# SCH_RTK2B_Micro_F9P_Breakout_Board_2023-.net
KiCad netlist of a schematic drawn in EasyEDA
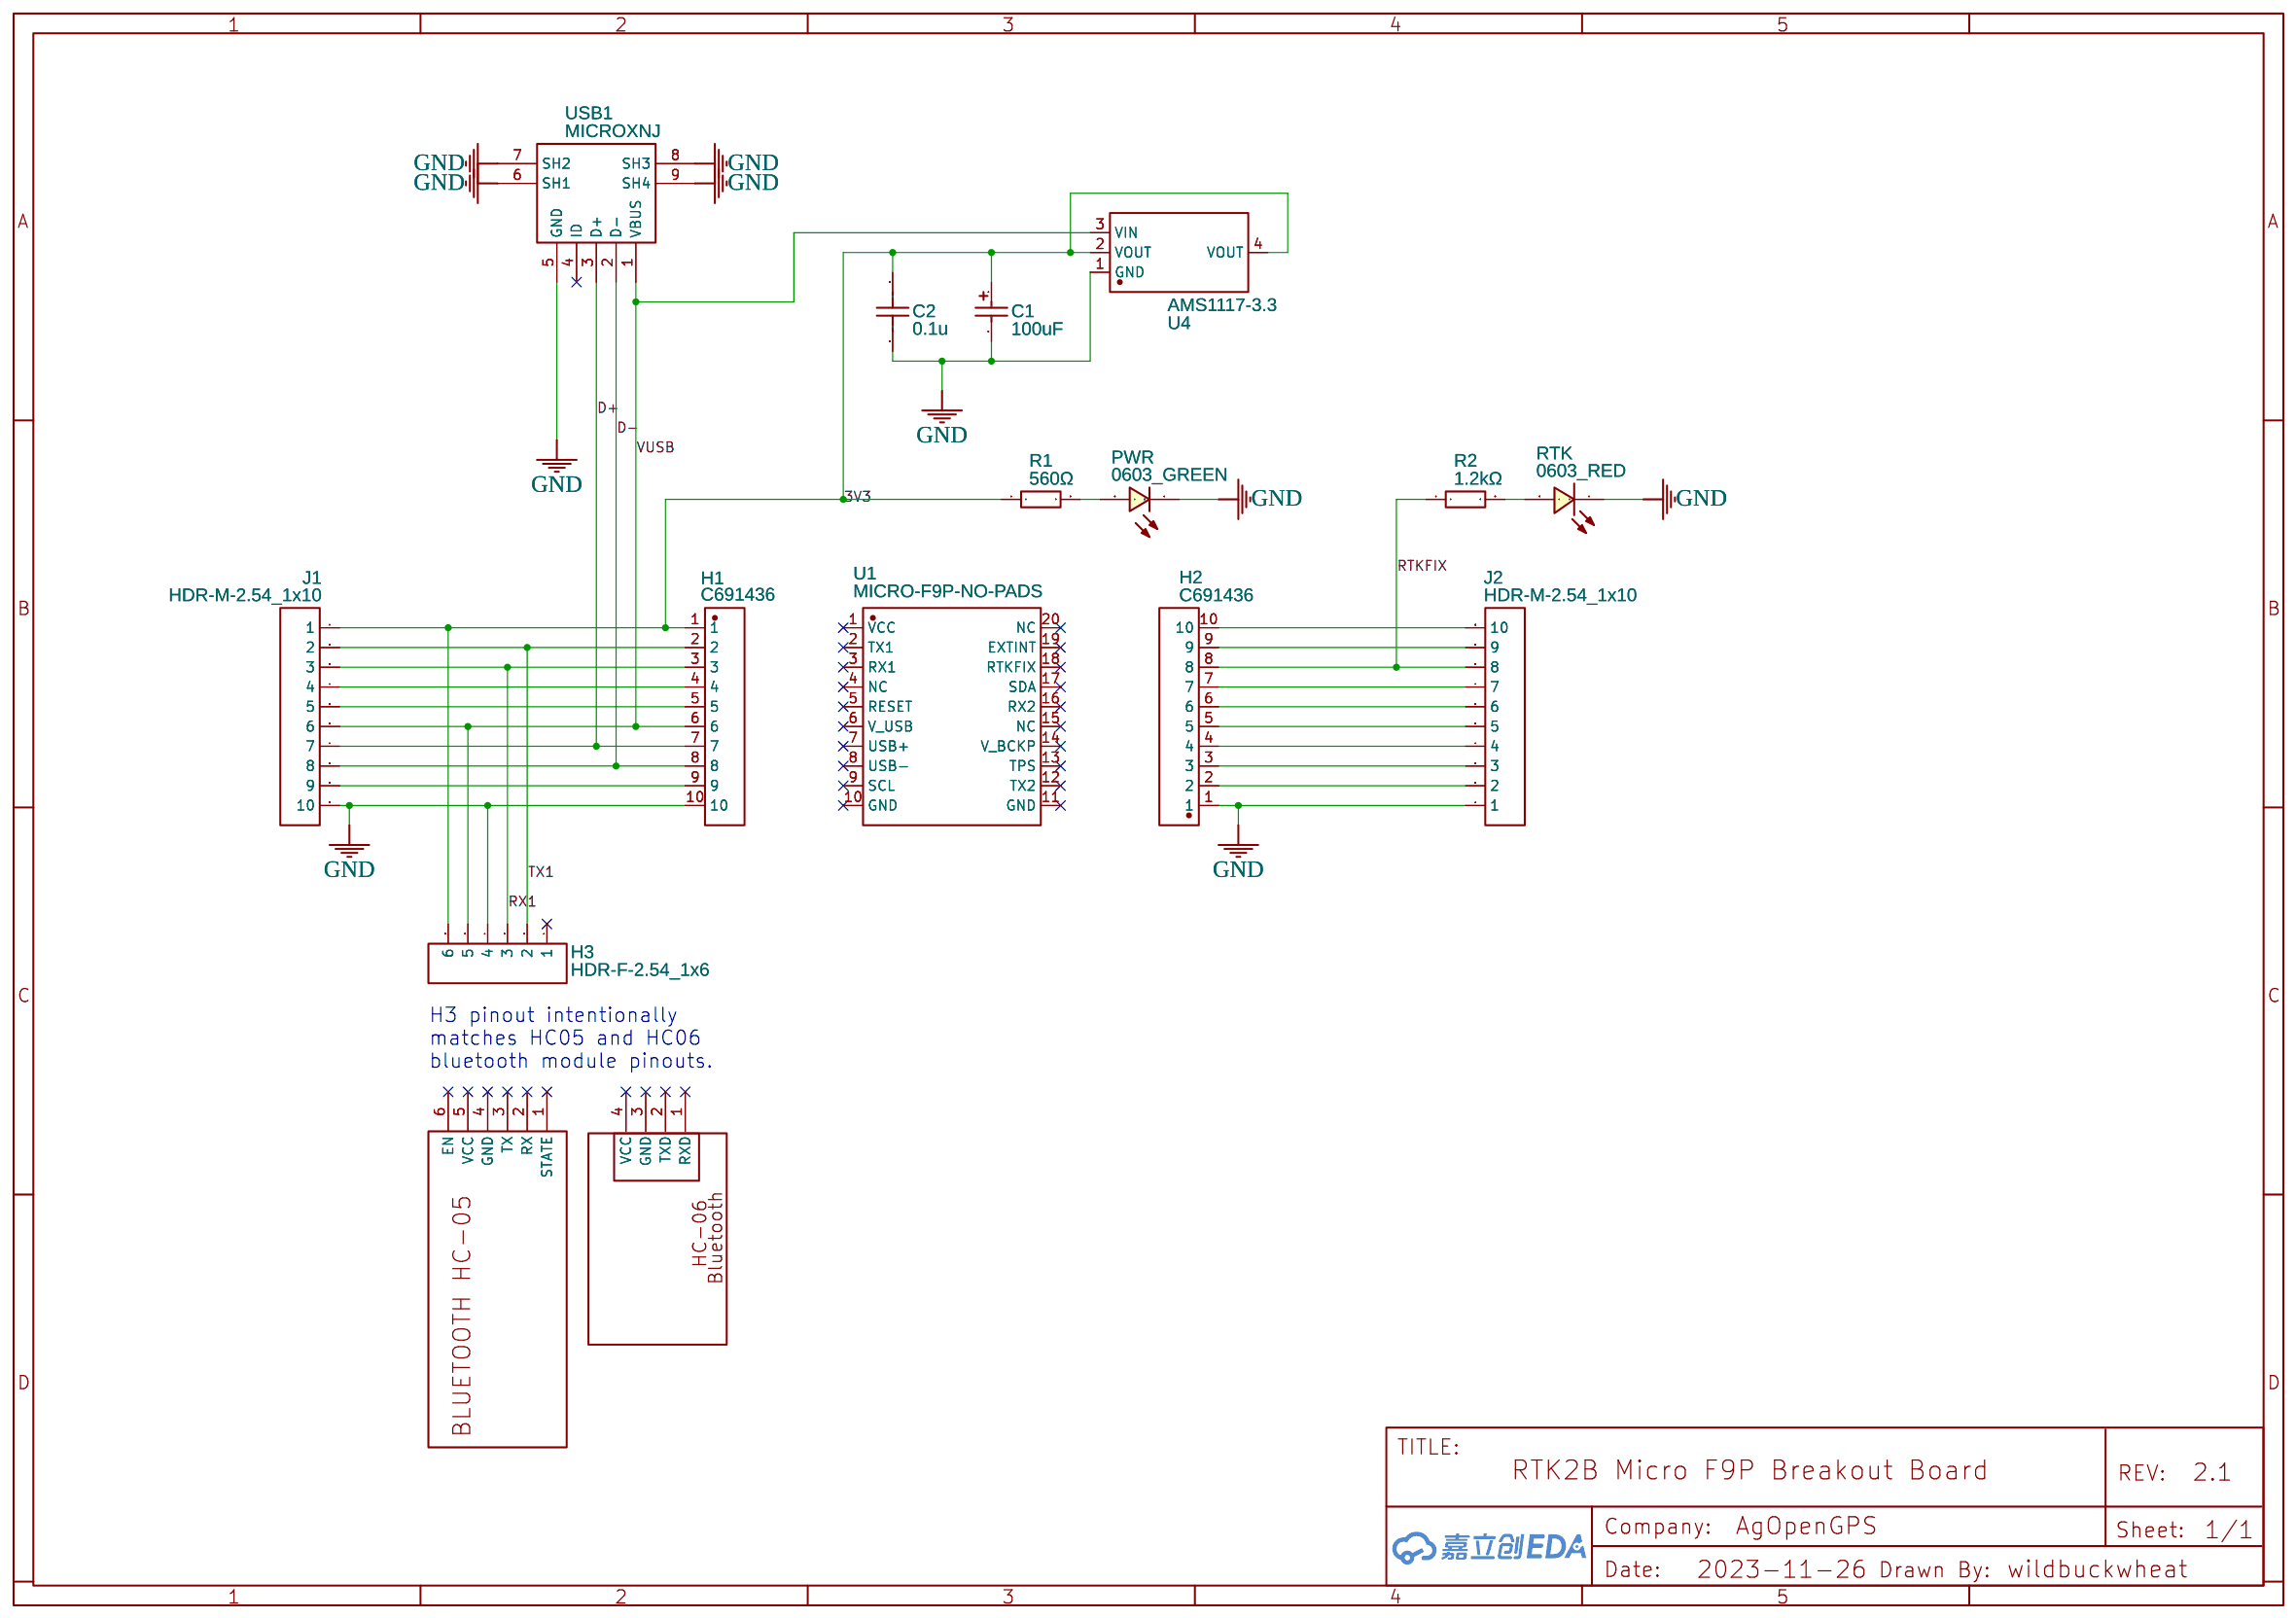
[diagram p0: schematic sheet]

(export (version "E")
  (design (tool "Eeschema 10.0.6"))
  (components
    (comp (ref "C1")
      (value "100uF")
      (fields (field (name "Manufacturer Part") "TAJB107K006RNJ") (field (name "Manufacturer") "Kyocera AVX"))
      (libsource (lib "") (part "TAJB107K006RNJ"))
    )
    (comp (ref "C2") (value "0.1u") (libsource (lib "") (part "C_0603_US")))
    (comp (ref "H1")
      (value "C691436")
      (fields (field (name "Manufacturer") "BOOMELE(Boom Precision Elec)"))
      (libsource (lib "") (part "C691436"))
    )
    (comp (ref "H2")
      (value "C691436")
      (fields (field (name "Manufacturer") "BOOMELE(Boom Precision Elec)"))
      (libsource (lib "") (part "C691436_1"))
    )
    (comp (ref "H3") (value "HDR-F-2.54_1x6") (libsource (lib "") (part "HDR-F-2.54_1x6")))
    (comp (ref "J1") (value "HDR-M-2.54_1x10") (libsource (lib "") (part "HDR-M-2.54_1x10")))
    (comp (ref "J2") (value "HDR-M-2.54_1x10") (libsource (lib "") (part "HDR-M-2.54_1x10_1")))
    (comp (ref "MK1") (value "Modulo_Bluetooth_HC-06") (libsource (lib "") (part "Modulo_Bluetooth_HC-06")))
    (comp (ref "PWR")
      (value "0603_GREEN")
      (fields
        (field (name "Manufacturer Part") "19-217/GHC-YR1S2/3T")
        (field (name "Manufacturer") "EVERLIGHT(亿光)")
      )
      (libsource (lib "") (part "19-217/GHC-YR1S2/3T-GREEN"))
    )
    (comp (ref "R1")
      (value "560Ω")
      (fields
        (field (name "Manufacturer Part") "0603WAF5600T5E")
        (field (name "Manufacturer") "UNI-ROYAL(厚声)")
      )
      (libsource (lib "") (part "0603WAF5600T5E"))
    )
    (comp (ref "R2")
      (value "1.2kΩ")
      (fields
        (field (name "Manufacturer Part") "0603WAF1201T5E")
        (field (name "Manufacturer") "UNI-ROYAL(厚声)")
      )
      (libsource (lib "") (part "0603WAF1201T5E"))
    )
    (comp (ref "RTK")
      (value "0603_RED")
      (fields (field (name "Manufacturer Part") "KT-0603R"))
      (libsource (lib "") (part "KT-0603R-RED"))
    )
    (comp (ref "U1") (value "MICRO-F9P-NO-PADS") (libsource (lib "") (part "MICRO-F9P-NO-PADS")))
    (comp (ref "U2")
      (value "BLUETOOTH HC05 COPY")
      (fields (field (name "Manufacturer Part") "BLUETOOTH HC05"))
      (libsource (lib "") (part "BLUETOOTH HC05 COPY"))
    )
    (comp (ref "U4")
      (value "AMS1117-3.3")
      (fields (field (name "Manufacturer") "AMS"))
      (libsource (lib "") (part "AMS1117-3.3"))
    )
    (comp (ref "USB1")
      (value "MICROXNJ")
      (fields (field (name "Manufacturer Part") "MicroXNJ") (field (name "Manufacturer") "SHOU HAN(首韩)"))
      (libsource (lib "") (part "MICROXNJ"))
    )
  )
  (nets
    (net (code "1") (name "/3V3") (class "Default")
      (node (ref "C1") (pin "1") (pinfunction "1_1") (pintype "input"))
      (node (ref "C2") (pin "2") (pinfunction "2_2") (pintype "unspecified"))
      (node (ref "H1") (pin "1") (pinfunction "1_1") (pintype "unspecified"))
      (node (ref "H3") (pin "6") (pinfunction "6_6") (pintype "input"))
      (node (ref "J1") (pin "1") (pinfunction "1_1") (pintype "unspecified"))
      (node (ref "R1") (pin "1") (pinfunction "1_1") (pintype "input"))
      (node (ref "U4") (pin "2") (pinfunction "VOUT_2") (pintype "unspecified"))
      (node (ref "U4") (pin "4") (pinfunction "VOUT_4") (pintype "unspecified"))
    )
    (net (code "2") (name "/D+") (class "Default")
      (node (ref "H1") (pin "7") (pinfunction "7_7") (pintype "unspecified"))
      (node (ref "J1") (pin "7") (pinfunction "7_7") (pintype "unspecified"))
      (node (ref "USB1") (pin "3") (pinfunction "D+_3") (pintype "unspecified"))
    )
    (net (code "3") (name "/D-") (class "Default")
      (node (ref "H1") (pin "8") (pinfunction "8_8") (pintype "unspecified"))
      (node (ref "J1") (pin "8") (pinfunction "8_8") (pintype "unspecified"))
      (node (ref "USB1") (pin "2") (pinfunction "D-_2") (pintype "unspecified"))
    )
    (net (code "4") (name "/RTKFIX") (class "Default")
      (node (ref "H2") (pin "8") (pinfunction "8_8") (pintype "unspecified"))
      (node (ref "J2") (pin "8") (pinfunction "8_8") (pintype "unspecified"))
      (node (ref "R2") (pin "1") (pinfunction "1_1") (pintype "input"))
    )
    (net (code "5") (name "/RX1") (class "Default")
      (node (ref "H1") (pin "3") (pinfunction "3_3") (pintype "unspecified"))
      (node (ref "H3") (pin "3") (pinfunction "3_3") (pintype "input"))
      (node (ref "J1") (pin "3") (pinfunction "3_3") (pintype "unspecified"))
    )
    (net (code "6") (name "/TX1") (class "Default")
      (node (ref "H1") (pin "2") (pinfunction "2_2") (pintype "unspecified"))
      (node (ref "H3") (pin "2") (pinfunction "2_2") (pintype "input"))
      (node (ref "J1") (pin "2") (pinfunction "2_2") (pintype "unspecified"))
    )
    (net (code "7") (name "/VUSB") (class "Default")
      (node (ref "H1") (pin "6") (pinfunction "6_6") (pintype "unspecified"))
      (node (ref "H3") (pin "5") (pinfunction "5_5") (pintype "input"))
      (node (ref "J1") (pin "6") (pinfunction "6_6") (pintype "unspecified"))
      (node (ref "U4") (pin "3") (pinfunction "VIN_3") (pintype "unspecified"))
      (node (ref "USB1") (pin "1") (pinfunction "VBUS_1") (pintype "unspecified"))
    )
    (net (code "8") (name "GND") (class "Default")
      (node (ref "C1") (pin "2") (pinfunction "2_2") (pintype "input"))
      (node (ref "C2") (pin "1") (pinfunction "1_1") (pintype "unspecified"))
      (node (ref "H1") (pin "10") (pinfunction "10_10") (pintype "unspecified"))
      (node (ref "H2") (pin "1") (pinfunction "1_1") (pintype "unspecified"))
      (node (ref "H3") (pin "4") (pinfunction "4_4") (pintype "input"))
      (node (ref "J1") (pin "10") (pinfunction "10_10") (pintype "unspecified"))
      (node (ref "J2") (pin "1") (pinfunction "1_1") (pintype "unspecified"))
      (node (ref "PWR") (pin "1") (pinfunction "C_1") (pintype "input"))
      (node (ref "RTK") (pin "1") (pinfunction "K_1") (pintype "unspecified"))
      (node (ref "U4") (pin "1") (pinfunction "GND_1") (pintype "unspecified"))
      (node (ref "USB1") (pin "5") (pinfunction "GND_5") (pintype "unspecified"))
      (node (ref "USB1") (pin "6") (pinfunction "SH1_6") (pintype "unspecified"))
      (node (ref "USB1") (pin "7") (pinfunction "SH2_7") (pintype "unspecified"))
      (node (ref "USB1") (pin "8") (pinfunction "SH3_8") (pintype "unspecified"))
      (node (ref "USB1") (pin "9") (pinfunction "SH4_9") (pintype "unspecified"))
    )
    (net (code "9") (name "Net-(H1-Pad4)") (class "Default")
      (node (ref "H1") (pin "4") (pinfunction "4_4") (pintype "unspecified"))
      (node (ref "J1") (pin "4") (pinfunction "4_4") (pintype "unspecified"))
    )
    (net (code "10") (name "Net-(H1-Pad5)") (class "Default")
      (node (ref "H1") (pin "5") (pinfunction "5_5") (pintype "unspecified"))
      (node (ref "J1") (pin "5") (pinfunction "5_5") (pintype "unspecified"))
    )
    (net (code "11") (name "Net-(H1-Pad9)") (class "Default")
      (node (ref "H1") (pin "9") (pinfunction "9_9") (pintype "unspecified"))
      (node (ref "J1") (pin "9") (pinfunction "9_9") (pintype "unspecified"))
    )
    (net (code "12") (name "Net-(H2-Pad2)") (class "Default")
      (node (ref "H2") (pin "2") (pinfunction "2_2") (pintype "unspecified"))
      (node (ref "J2") (pin "2") (pinfunction "2_2") (pintype "unspecified"))
    )
    (net (code "13") (name "Net-(H2-Pad3)") (class "Default")
      (node (ref "H2") (pin "3") (pinfunction "3_3") (pintype "unspecified"))
      (node (ref "J2") (pin "3") (pinfunction "3_3") (pintype "unspecified"))
    )
    (net (code "14") (name "Net-(H2-Pad4)") (class "Default")
      (node (ref "H2") (pin "4") (pinfunction "4_4") (pintype "unspecified"))
      (node (ref "J2") (pin "4") (pinfunction "4_4") (pintype "unspecified"))
    )
    (net (code "15") (name "Net-(H2-Pad5)") (class "Default")
      (node (ref "H2") (pin "5") (pinfunction "5_5") (pintype "unspecified"))
      (node (ref "J2") (pin "5") (pinfunction "5_5") (pintype "unspecified"))
    )
    (net (code "16") (name "Net-(H2-Pad6)") (class "Default")
      (node (ref "H2") (pin "6") (pinfunction "6_6") (pintype "unspecified"))
      (node (ref "J2") (pin "6") (pinfunction "6_6") (pintype "unspecified"))
    )
    (net (code "17") (name "Net-(H2-Pad7)") (class "Default")
      (node (ref "H2") (pin "7") (pinfunction "7_7") (pintype "unspecified"))
      (node (ref "J2") (pin "7") (pinfunction "7_7") (pintype "unspecified"))
    )
    (net (code "18") (name "Net-(H2-Pad9)") (class "Default")
      (node (ref "H2") (pin "9") (pinfunction "9_9") (pintype "unspecified"))
      (node (ref "J2") (pin "9") (pinfunction "9_9") (pintype "unspecified"))
    )
    (net (code "19") (name "Net-(H2-Pad10)") (class "Default")
      (node (ref "H2") (pin "10") (pinfunction "10_10") (pintype "unspecified"))
      (node (ref "J2") (pin "10") (pinfunction "10_10") (pintype "unspecified"))
    )
    (net (code "20") (name "Net-(PWR-A)") (class "Default")
      (node (ref "PWR") (pin "2") (pinfunction "A_2") (pintype "input"))
      (node (ref "R1") (pin "2") (pinfunction "2_2") (pintype "input"))
    )
    (net (code "21") (name "Net-(RTK-A)") (class "Default")
      (node (ref "R2") (pin "2") (pinfunction "2_2") (pintype "input"))
      (node (ref "RTK") (pin "2") (pinfunction "A_2") (pintype "unspecified"))
    )
    (net (code "22") (name "unconnected-(H3-Pad1)") (class "Default")
      (node (ref "H3") (pin "1") (pinfunction "1_1") (pintype "input+no_connect"))
    )
    (net (code "23") (name "unconnected-(MK1-GND-Pad3)") (class "Default")
      (node (ref "MK1") (pin "3") (pinfunction "GND_3") (pintype "unspecified+no_connect"))
    )
    (net (code "24") (name "unconnected-(MK1-RXD-Pad1)") (class "Default")
      (node (ref "MK1") (pin "1") (pinfunction "RXD_1") (pintype "unspecified+no_connect"))
    )
    (net (code "25") (name "unconnected-(MK1-TXD-Pad2)") (class "Default")
      (node (ref "MK1") (pin "2") (pinfunction "TXD_2") (pintype "unspecified+no_connect"))
    )
    (net (code "26") (name "unconnected-(MK1-VCC-Pad4)") (class "Default")
      (node (ref "MK1") (pin "4") (pinfunction "VCC_4") (pintype "unspecified+no_connect"))
    )
    (net (code "27") (name "unconnected-(U1-EXTINT-Pad19)") (class "Default")
      (node (ref "U1") (pin "19") (pinfunction "EXTINT_19") (pintype "unspecified+no_connect"))
    )
    (net (code "28") (name "unconnected-(U1-GND-Pad10)") (class "Default")
      (node (ref "U1") (pin "10") (pinfunction "GND_10") (pintype "unspecified+no_connect"))
    )
    (net (code "29") (name "unconnected-(U1-GND-Pad11)") (class "Default")
      (node (ref "U1") (pin "11") (pinfunction "GND_11") (pintype "unspecified+no_connect"))
    )
    (net (code "30") (name "unconnected-(U1-NC-Pad4)") (class "Default")
      (node (ref "U1") (pin "4") (pinfunction "NC_4") (pintype "unspecified+no_connect"))
    )
    (net (code "31") (name "unconnected-(U1-NC-Pad15)") (class "Default")
      (node (ref "U1") (pin "15") (pinfunction "NC_15") (pintype "unspecified+no_connect"))
    )
    (net (code "32") (name "unconnected-(U1-NC-Pad20)") (class "Default")
      (node (ref "U1") (pin "20") (pinfunction "NC_20") (pintype "unspecified+no_connect"))
    )
    (net (code "33") (name "unconnected-(U1-RESET-Pad5)") (class "Default")
      (node (ref "U1") (pin "5") (pinfunction "RESET_5") (pintype "unspecified+no_connect"))
    )
    (net (code "34") (name "unconnected-(U1-RTKFIX-Pad18)") (class "Default")
      (node (ref "U1") (pin "18") (pinfunction "RTKFIX_18") (pintype "unspecified+no_connect"))
    )
    (net (code "35") (name "unconnected-(U1-RX1-Pad3)") (class "Default")
      (node (ref "U1") (pin "3") (pinfunction "RX1_3") (pintype "unspecified+no_connect"))
    )
    (net (code "36") (name "unconnected-(U1-RX2-Pad16)") (class "Default")
      (node (ref "U1") (pin "16") (pinfunction "RX2_16") (pintype "unspecified+no_connect"))
    )
    (net (code "37") (name "unconnected-(U1-SCL-Pad9)") (class "Default")
      (node (ref "U1") (pin "9") (pinfunction "SCL_9") (pintype "unspecified+no_connect"))
    )
    (net (code "38") (name "unconnected-(U1-SDA-Pad17)") (class "Default")
      (node (ref "U1") (pin "17") (pinfunction "SDA_17") (pintype "unspecified+no_connect"))
    )
    (net (code "39") (name "unconnected-(U1-TPS-Pad13)") (class "Default")
      (node (ref "U1") (pin "13") (pinfunction "TPS_13") (pintype "unspecified+no_connect"))
    )
    (net (code "40") (name "unconnected-(U1-TX1-Pad2)") (class "Default")
      (node (ref "U1") (pin "2") (pinfunction "TX1_2") (pintype "unspecified+no_connect"))
    )
    (net (code "41") (name "unconnected-(U1-TX2-Pad12)") (class "Default")
      (node (ref "U1") (pin "12") (pinfunction "TX2_12") (pintype "unspecified+no_connect"))
    )
    (net (code "42") (name "unconnected-(U1-USB+-Pad7)") (class "Default")
      (node (ref "U1") (pin "7") (pinfunction "USB+_7") (pintype "unspecified+no_connect"))
    )
    (net (code "43") (name "unconnected-(U1-USB--Pad8)") (class "Default")
      (node (ref "U1") (pin "8") (pinfunction "USB-_8") (pintype "unspecified+no_connect"))
    )
    (net (code "44") (name "unconnected-(U1-VCC-Pad1)") (class "Default")
      (node (ref "U1") (pin "1") (pinfunction "VCC_1") (pintype "unspecified+no_connect"))
    )
    (net (code "45") (name "unconnected-(U1-V_BCKP-Pad14)") (class "Default")
      (node (ref "U1") (pin "14") (pinfunction "V_BCKP_14") (pintype "unspecified+no_connect"))
    )
    (net (code "46") (name "unconnected-(U1-V_USB-Pad6)") (class "Default")
      (node (ref "U1") (pin "6") (pinfunction "V_USB_6") (pintype "unspecified+no_connect"))
    )
    (net (code "47") (name "unconnected-(U2-EN-Pad6)") (class "Default")
      (node (ref "U2") (pin "6") (pinfunction "EN_6") (pintype "unspecified+no_connect"))
    )
    (net (code "48") (name "unconnected-(U2-GND-Pad4)") (class "Default")
      (node (ref "U2") (pin "4") (pinfunction "GND_4") (pintype "unspecified+no_connect"))
    )
    (net (code "49") (name "unconnected-(U2-RX-Pad2)") (class "Default")
      (node (ref "U2") (pin "2") (pinfunction "RX_2") (pintype "unspecified+no_connect"))
    )
    (net (code "50") (name "unconnected-(U2-STATE-Pad1)") (class "Default")
      (node (ref "U2") (pin "1") (pinfunction "STATE_1") (pintype "unspecified+no_connect"))
    )
    (net (code "51") (name "unconnected-(U2-TX-Pad3)") (class "Default")
      (node (ref "U2") (pin "3") (pinfunction "TX_3") (pintype "unspecified+no_connect"))
    )
    (net (code "52") (name "unconnected-(U2-VCC-Pad5)") (class "Default")
      (node (ref "U2") (pin "5") (pinfunction "VCC_5") (pintype "unspecified+no_connect"))
    )
    (net (code "53") (name "unconnected-(USB1-ID-Pad4)") (class "Default")
      (node (ref "USB1") (pin "4") (pinfunction "ID_4") (pintype "unspecified+no_connect"))
    )
  )
)
